# sensor_GT.net
KiCad netlist of a schematic drawn in EAGLE
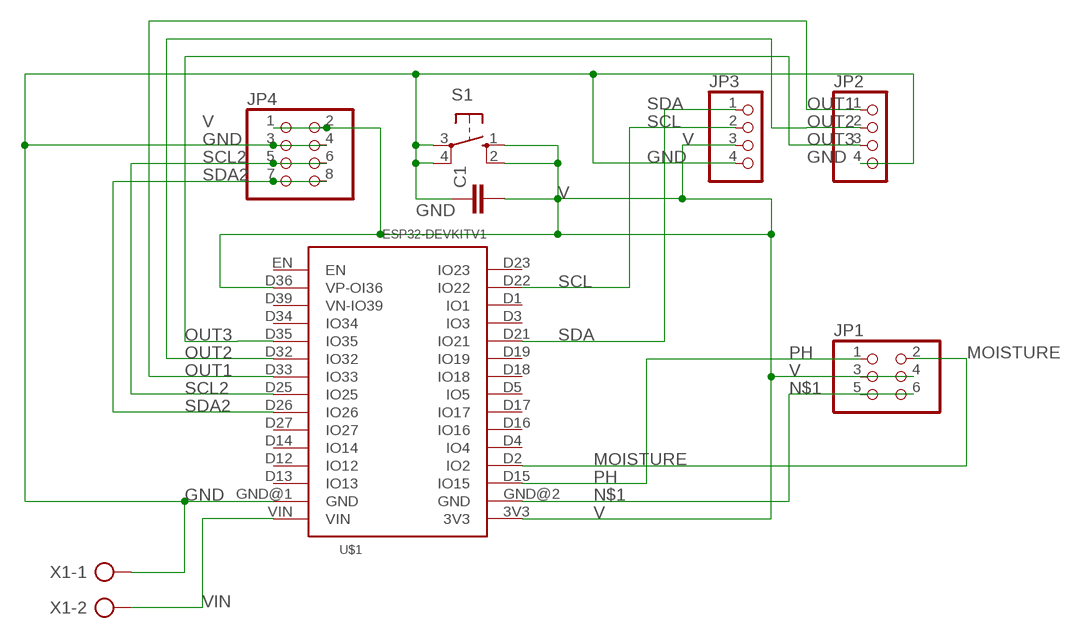
[diagram p0: schematic, sheet 1]

(export (version "E")
  (design (tool "Eeschema 10.0.6"))
  (components
    (comp (ref "C1")
      (value "C-EU050-030X075")
      (footprint "eagle-import:C050-030X075")
      (libsource (lib "eagle-import") (part "C-EU050-030X075"))
    )
    (comp (ref "JP1")
      (value "PINHD-2X3")
      (footprint "eagle-import:2X03")
      (libsource (lib "eagle-import") (part "PINHD-2X3"))
    )
    (comp (ref "JP2")
      (value "PINHD-1X4")
      (footprint "eagle-import:1X04")
      (libsource (lib "eagle-import") (part "PINHD-1X4"))
    )
    (comp (ref "JP3")
      (value "PINHD-1X4")
      (footprint "eagle-import:1X04")
      (libsource (lib "eagle-import") (part "PINHD-1X4"))
    )
    (comp (ref "JP4")
      (value "PINHD-2X4")
      (footprint "eagle-import:2X04")
      (libsource (lib "eagle-import") (part "PINHD-2X4"))
    )
    (comp (ref "S1")
      (value "10-XX")
      (footprint "eagle-import:B3F-10XX")
      (fields (field (name "MPN") "B3F-1000"))
      (libsource (lib "eagle-import") (part "10-XX"))
    )
    (comp (ref "U$1")
      (value "ESP32DEVKITV1")
      (footprint "eagle-import:ESP32-DEVKITV1")
      (libsource (lib "eagle-import") (part "ESP32DEVKITV1"))
    )
    (comp (ref "X1")
      (value "AK300/2")
      (footprint "eagle-import:AK300_2")
      (libsource (lib "eagle-import") (part "AK300/2"))
    )
  )
  (nets
    (net (code "1") (name "/GND") (class "Default")
      (node (ref "C1") (pin "1") (pinfunction "1_1") (pintype "passive"))
      (node (ref "JP2") (pin "4") (pinfunction "4_4") (pintype "passive"))
      (node (ref "JP3") (pin "4") (pinfunction "4_4") (pintype "passive"))
      (node (ref "JP4") (pin "3") (pinfunction "3_3") (pintype "passive"))
      (node (ref "JP4") (pin "4") (pinfunction "4_4") (pintype "passive"))
      (node (ref "S1") (pin "3") (pinfunction "P_3") (pintype "passive"))
      (node (ref "S1") (pin "4") (pinfunction "P1_4") (pintype "passive"))
      (node (ref "U$1") (pin "GND@1") (pinfunction "GND_GND@1") (pintype "bidirectional"))
      (node (ref "X1") (pin "1") (pinfunction "KL_1") (pintype "passive"))
    )
    (net (code "2") (name "/MOISTURE") (class "Default")
      (node (ref "JP1") (pin "2") (pinfunction "2_2") (pintype "passive"))
      (node (ref "U$1") (pin "D2") (pinfunction "IO2_D2") (pintype "bidirectional"))
    )
    (net (code "3") (name "/N$1") (class "Default")
      (node (ref "JP1") (pin "5") (pinfunction "5_5") (pintype "passive"))
      (node (ref "JP1") (pin "6") (pinfunction "6_6") (pintype "passive"))
      (node (ref "U$1") (pin "GND@2") (pinfunction "GND_GND@2") (pintype "bidirectional"))
    )
    (net (code "4") (name "/OUT1") (class "Default")
      (node (ref "JP2") (pin "1") (pinfunction "1_1") (pintype "passive"))
      (node (ref "U$1") (pin "D33") (pinfunction "IO33_D33") (pintype "bidirectional"))
    )
    (net (code "5") (name "/OUT2") (class "Default")
      (node (ref "JP2") (pin "2") (pinfunction "2_2") (pintype "passive"))
      (node (ref "U$1") (pin "D32") (pinfunction "IO32_D32") (pintype "bidirectional"))
    )
    (net (code "6") (name "/OUT3") (class "Default")
      (node (ref "JP2") (pin "3") (pinfunction "3_3") (pintype "passive"))
      (node (ref "U$1") (pin "D35") (pinfunction "IO35_D35") (pintype "bidirectional"))
    )
    (net (code "7") (name "/PH") (class "Default")
      (node (ref "JP1") (pin "1") (pinfunction "1_1") (pintype "passive"))
      (node (ref "U$1") (pin "D15") (pinfunction "IO15_D15") (pintype "bidirectional"))
    )
    (net (code "8") (name "/SCL") (class "Default")
      (node (ref "JP3") (pin "2") (pinfunction "2_2") (pintype "passive"))
      (node (ref "U$1") (pin "D22") (pinfunction "IO22_D22") (pintype "bidirectional"))
    )
    (net (code "9") (name "/SCL2") (class "Default")
      (node (ref "JP4") (pin "5") (pinfunction "5_5") (pintype "passive"))
      (node (ref "JP4") (pin "6") (pinfunction "6_6") (pintype "passive"))
      (node (ref "U$1") (pin "D25") (pinfunction "IO25_D25") (pintype "bidirectional"))
    )
    (net (code "10") (name "/SDA") (class "Default")
      (node (ref "JP3") (pin "1") (pinfunction "1_1") (pintype "passive"))
      (node (ref "U$1") (pin "D21") (pinfunction "IO21_D21") (pintype "bidirectional"))
    )
    (net (code "11") (name "/SDA2") (class "Default")
      (node (ref "JP4") (pin "7") (pinfunction "7_7") (pintype "passive"))
      (node (ref "JP4") (pin "8") (pinfunction "8_8") (pintype "passive"))
      (node (ref "U$1") (pin "D26") (pinfunction "IO26_D26") (pintype "bidirectional"))
    )
    (net (code "12") (name "/V") (class "Default")
      (node (ref "C1") (pin "2") (pinfunction "2_2") (pintype "passive"))
      (node (ref "JP1") (pin "3") (pinfunction "3_3") (pintype "passive"))
      (node (ref "JP1") (pin "4") (pinfunction "4_4") (pintype "passive"))
      (node (ref "JP3") (pin "3") (pinfunction "3_3") (pintype "passive"))
      (node (ref "JP4") (pin "1") (pinfunction "1_1") (pintype "passive"))
      (node (ref "JP4") (pin "2") (pinfunction "2_2") (pintype "passive"))
      (node (ref "S1") (pin "1") (pinfunction "S_1") (pintype "passive"))
      (node (ref "S1") (pin "2") (pinfunction "S1_2") (pintype "passive"))
      (node (ref "U$1") (pin "3V3") (pinfunction "3V3_3V3") (pintype "bidirectional"))
      (node (ref "U$1") (pin "D36") (pinfunction "VP-OI36_D36") (pintype "bidirectional"))
    )
    (net (code "13") (name "/VIN") (class "Default")
      (node (ref "U$1") (pin "VIN") (pinfunction "VIN_VIN") (pintype "bidirectional"))
      (node (ref "X1") (pin "2") (pinfunction "KL_2") (pintype "passive"))
    )
    (net (code "14") (name "unconnected-(U$1-IO1-PadD1)") (class "Default")
      (node (ref "U$1") (pin "D1") (pinfunction "IO1_D1") (pintype "bidirectional"))
    )
    (net (code "15") (name "unconnected-(U$1-IO3-PadD3)") (class "Default")
      (node (ref "U$1") (pin "D3") (pinfunction "IO3_D3") (pintype "bidirectional"))
    )
    (net (code "16") (name "unconnected-(U$1-IO4-PadD4)") (class "Default")
      (node (ref "U$1") (pin "D4") (pinfunction "IO4_D4") (pintype "bidirectional"))
    )
    (net (code "17") (name "unconnected-(U$1-IO5-PadD5)") (class "Default")
      (node (ref "U$1") (pin "D5") (pinfunction "IO5_D5") (pintype "bidirectional"))
    )
    (net (code "18") (name "unconnected-(U$1-IO12-PadD12)") (class "Default")
      (node (ref "U$1") (pin "D12") (pinfunction "IO12_D12") (pintype "bidirectional"))
    )
    (net (code "19") (name "unconnected-(U$1-IO13-PadD13)") (class "Default")
      (node (ref "U$1") (pin "D13") (pinfunction "IO13_D13") (pintype "bidirectional"))
    )
    (net (code "20") (name "unconnected-(U$1-IO14-PadD14)") (class "Default")
      (node (ref "U$1") (pin "D14") (pinfunction "IO14_D14") (pintype "bidirectional"))
    )
    (net (code "21") (name "unconnected-(U$1-IO16-PadD16)") (class "Default")
      (node (ref "U$1") (pin "D16") (pinfunction "IO16_D16") (pintype "bidirectional"))
    )
    (net (code "22") (name "unconnected-(U$1-IO17-PadD17)") (class "Default")
      (node (ref "U$1") (pin "D17") (pinfunction "IO17_D17") (pintype "bidirectional"))
    )
    (net (code "23") (name "unconnected-(U$1-IO18-PadD18)") (class "Default")
      (node (ref "U$1") (pin "D18") (pinfunction "IO18_D18") (pintype "bidirectional"))
    )
    (net (code "24") (name "unconnected-(U$1-IO19-PadD19)") (class "Default")
      (node (ref "U$1") (pin "D19") (pinfunction "IO19_D19") (pintype "bidirectional"))
    )
    (net (code "25") (name "unconnected-(U$1-IO23-PadD23)") (class "Default")
      (node (ref "U$1") (pin "D23") (pinfunction "IO23_D23") (pintype "bidirectional"))
    )
    (net (code "26") (name "unconnected-(U$1-IO27-PadD27)") (class "Default")
      (node (ref "U$1") (pin "D27") (pinfunction "IO27_D27") (pintype "bidirectional"))
    )
    (net (code "27") (name "unconnected-(U$1-IO34-PadD34)") (class "Default")
      (node (ref "U$1") (pin "D34") (pinfunction "IO34_D34") (pintype "bidirectional"))
    )
    (net (code "28") (name "unconnected-(U$1-PadEN)") (class "Default")
      (node (ref "U$1") (pin "EN") (pinfunction "EN_EN") (pintype "bidirectional"))
    )
    (net (code "29") (name "unconnected-(U$1-VN-IO39-PadD39)") (class "Default")
      (node (ref "U$1") (pin "D39") (pinfunction "VN-IO39_D39") (pintype "bidirectional"))
    )
  )
)
